# MPCButton.net
KiCad netlist of a schematic drawn in Altium Designer
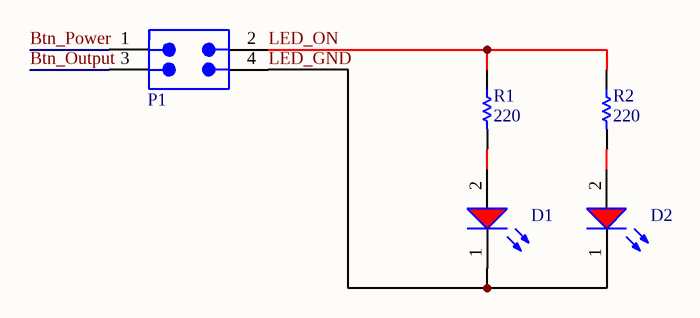
[diagram p0: MPCButton.SchDoc]

(export (version "E")
  (design (tool "Eeschema 10.0.6"))
  (components
    (comp (ref "D1")
      (value "Red, 2V, 120°")
      (footprint "WL-SMCC_0603_150060xx73220")
      (description "WL-SMCC Mono-color Chip LED Compact, SMT, size 0603, Red, 2V, 120°")
      (fields
        (field (name "MANUFACTURER PART NUMBER") "150060RS73220")
        (field (name "MANUFACTURER") "Wurth Elektronik")
      )
      (libsource (lib "Altium_WL-SMCC (rev24a)") (part "150060RS73220"))
    )
    (comp (ref "D2")
      (value "Red, 2V, 120°")
      (footprint "WL-SMCC_0603_150060xx73220")
      (description "WL-SMCC Mono-color Chip LED Compact, SMT, size 0603, Red, 2V, 120°")
      (fields
        (field (name "MANUFACTURER PART NUMBER") "150060RS73220")
        (field (name "MANUFACTURER") "Wurth Elektronik")
      )
      (libsource (lib "Altium_WL-SMCC (rev24a)") (part "150060RS73220"))
    )
    (comp (ref "P1")
      (value "62100421921")
      (footprint "62100421921")
      (description "WR-PHD Pin Header, SMT, Vertical, pitch 2mm, 2 Row, 4P")
      (fields (field (name "MANUFACTURER") "Wurth Elektronik"))
      (libsource (lib "Wurth_WR-PHD (rev24a)") (part "62100421921"))
    )
    (comp (ref "R1")
      (value "220")
      (footprint "RESC0603(1608)_N")
      (description "RES")
      (libsource (lib "Passive SMD") (part "RES"))
    )
    (comp (ref "R2")
      (value "220")
      (footprint "RESC0603(1608)_N")
      (description "RES")
      (libsource (lib "Passive SMD") (part "RES"))
    )
  )
  (nets
    (net (code "1") (name "/Btn_Output") (class "Default")
      (node (ref "P1") (pin "3") (pinfunction "3_3") (pintype "passive"))
    )
    (net (code "2") (name "/Btn_Power") (class "Default")
      (node (ref "P1") (pin "1") (pinfunction "1_1") (pintype "passive"))
    )
    (net (code "3") (name "/LED_GND") (class "Default")
      (node (ref "D1") (pin "1") (pinfunction "K_1") (pintype "passive"))
      (node (ref "D2") (pin "1") (pinfunction "K_1") (pintype "passive"))
      (node (ref "P1") (pin "4") (pinfunction "4_4") (pintype "passive"))
    )
    (net (code "4") (name "/LED_ON") (class "Default")
      (node (ref "P1") (pin "2") (pinfunction "2_2") (pintype "passive"))
      (node (ref "R1") (pin "1") (pinfunction "1_1") (pintype "passive"))
      (node (ref "R2") (pin "1") (pinfunction "1_1") (pintype "passive"))
    )
    (net (code "5") (name "Net-(D1-A)") (class "Default")
      (node (ref "D1") (pin "2") (pinfunction "A_2") (pintype "passive"))
      (node (ref "R1") (pin "2") (pinfunction "2_2") (pintype "passive"))
    )
    (net (code "6") (name "Net-(D2-A)") (class "Default")
      (node (ref "D2") (pin "2") (pinfunction "A_2") (pintype "passive"))
      (node (ref "R2") (pin "2") (pinfunction "2_2") (pintype "passive"))
    )
  )
)
